# MAG_MMC5983MA.net
KiCad netlist of a schematic drawn in Altium Designer
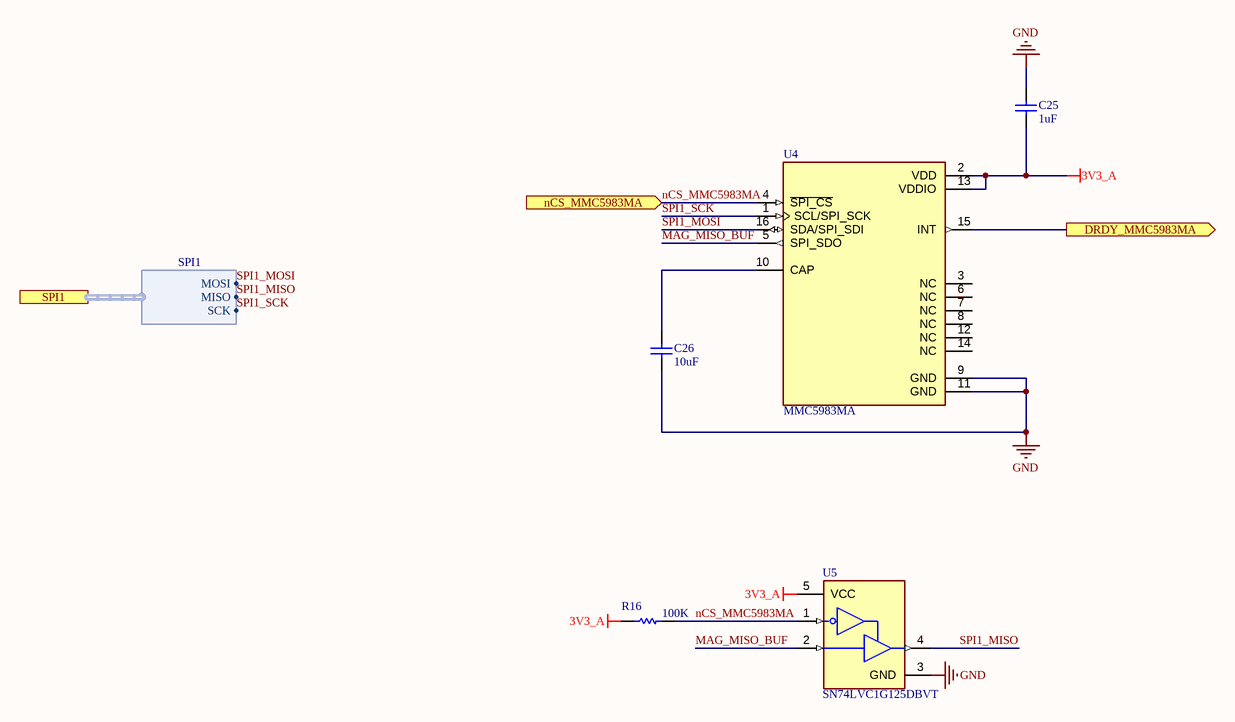
[diagram p0: MAG_MMC5983MA.SchDoc]

(export (version "E")
  (design (tool "Eeschema 10.0.6"))
  (components
    (comp (ref "C25")
      (value "1uF")
      (footprint "CAPC1608X90X35LL15T15")
      (fields (field (name "MANUFACTURER") "Kemet") (field (name "PART NUMBER") "C0603C105K4RACTU"))
      (libsource (lib "Altium Content Vault") (part "CAP"))
    )
    (comp (ref "C26")
      (value "10uF")
      (footprint "CAPC2013X145X50LL20T25")
      (fields (field (name "MANUFACTURER") "Kemet") (field (name "PART NUMBER") "C0805C106K8RACTU"))
      (libsource (lib "Altium Content Vault") (part "CAP"))
    )
    (comp (ref "R16")
      (value "100K")
      (footprint "RESC1608X55X30ML20T10")
      (fields (field (name "PART NUMBER") "RK73B1JTTD104J") (field (name "MANUFACTURER") "KOA Speer"))
      (libsource (lib "Altium Content Vault") (part "RES"))
    )
    (comp (ref "U4")
      (value "MMC5983MA")
      (footprint "PQFN50P300X300X100-16N")
      (description "MMC5983 series Magnetic, Magnetometer Sensor Evaluation Board")
      (fields (field (name "MF") "Memsic Inc."))
      (libsource (lib "Hitesh Bhoyar") (part "MMC5983MA"))
    )
    (comp (ref "U5")
      (value "SN74LVC1G125DBVT")
      (footprint "FP-DBV0005A-MFG")
      (description "IC BUF NON-INVERT 5.5V SOT23-5")
      (fields
        (field (name "OCTOPART") "https://octopart.com/sn74lvc1g125dbvt-texas+instruments-1006799")
        (field (name "MANUFACTURER") "Texas Instruments")
      )
      (libsource (lib "Altium Content Vault") (part "58769f6d8490b1ac5b52b989db43374"))
    )
  )
  (nets
    (net (code "2") (name "/DRDY_MMC5983MA") (class "Default")
      (node (ref "U4") (pin "15") (pinfunction "INT_15") (pintype "output"))
    )
    (net (code "3") (name "/MAG_MISO_BUF") (class "Default")
      (node (ref "U4") (pin "5") (pinfunction "SPI_SDO_5") (pintype "output"))
      (node (ref "U5") (pin "2") (pinfunction "A_2") (pintype "input"))
    )
    (net (code "4") (name "/SPI1_MISO") (class "Default")
      (node (ref "U5") (pin "4") (pinfunction "Y_4") (pintype "output"))
    )
    (net (code "5") (name "/SPI1_MOSI") (class "Default")
      (node (ref "U4") (pin "16") (pinfunction "SDA/SPI_SDI_16") (pintype "bidirectional"))
    )
    (net (code "6") (name "/SPI1_SCK") (class "Default")
      (node (ref "U4") (pin "1") (pinfunction "SCL/SPI_SCK_1") (pintype "input"))
    )
    (net (code "7") (name "/nCS_MMC5983MA") (class "Default")
      (node (ref "R16") (pin "1") (pinfunction "1_1") (pintype "passive"))
      (node (ref "U4") (pin "4") (pinfunction "~{SPI_CS}_4") (pintype "input"))
      (node (ref "U5") (pin "1") (pinfunction "~{OE}_1") (pintype "input"))
    )
    (net (code "9") (name "3V3_A") (class "Default")
      (node (ref "C25") (pin "1") (pinfunction "1_1") (pintype "passive"))
      (node (ref "R16") (pin "2") (pinfunction "2_2") (pintype "passive"))
      (node (ref "U4") (pin "13") (pinfunction "VDDIO_13") (pintype "power_in"))
      (node (ref "U4") (pin "2") (pinfunction "VDD_2") (pintype "power_in"))
      (node (ref "U5") (pin "5") (pinfunction "VCC_5") (pintype "power_in"))
    )
    (net (code "10") (name "GND") (class "Default")
      (node (ref "C25") (pin "2") (pinfunction "2_2") (pintype "passive"))
      (node (ref "C26") (pin "2") (pinfunction "2_2") (pintype "passive"))
      (node (ref "U4") (pin "11") (pinfunction "GND_11") (pintype "power_in"))
      (node (ref "U4") (pin "9") (pinfunction "GND_9") (pintype "power_in"))
      (node (ref "U5") (pin "3") (pinfunction "GND_3") (pintype "power_in"))
    )
    (net (code "11") (name "Net-(U4-CAP)") (class "Default")
      (node (ref "C26") (pin "1") (pinfunction "1_1") (pintype "passive"))
      (node (ref "U4") (pin "10") (pinfunction "CAP_10") (pintype "passive"))
    )
    (net (code "12") (name "unconnected-(U4-NC-Pad3)") (class "Default")
      (node (ref "U4") (pin "3") (pinfunction "NC_3") (pintype "passive"))
    )
    (net (code "13") (name "unconnected-(U4-NC-Pad6)") (class "Default")
      (node (ref "U4") (pin "6") (pinfunction "NC_6") (pintype "passive"))
    )
    (net (code "14") (name "unconnected-(U4-NC-Pad7)") (class "Default")
      (node (ref "U4") (pin "7") (pinfunction "NC_7") (pintype "passive"))
    )
    (net (code "15") (name "unconnected-(U4-NC-Pad8)") (class "Default")
      (node (ref "U4") (pin "8") (pinfunction "NC_8") (pintype "passive"))
    )
    (net (code "16") (name "unconnected-(U4-NC-Pad12)") (class "Default")
      (node (ref "U4") (pin "12") (pinfunction "NC_12") (pintype "passive"))
    )
    (net (code "17") (name "unconnected-(U4-NC-Pad14)") (class "Default")
      (node (ref "U4") (pin "14") (pinfunction "NC_14") (pintype "passive"))
    )
  )
)
